# MCU.net
KiCad netlist of a schematic drawn in Altium Designer
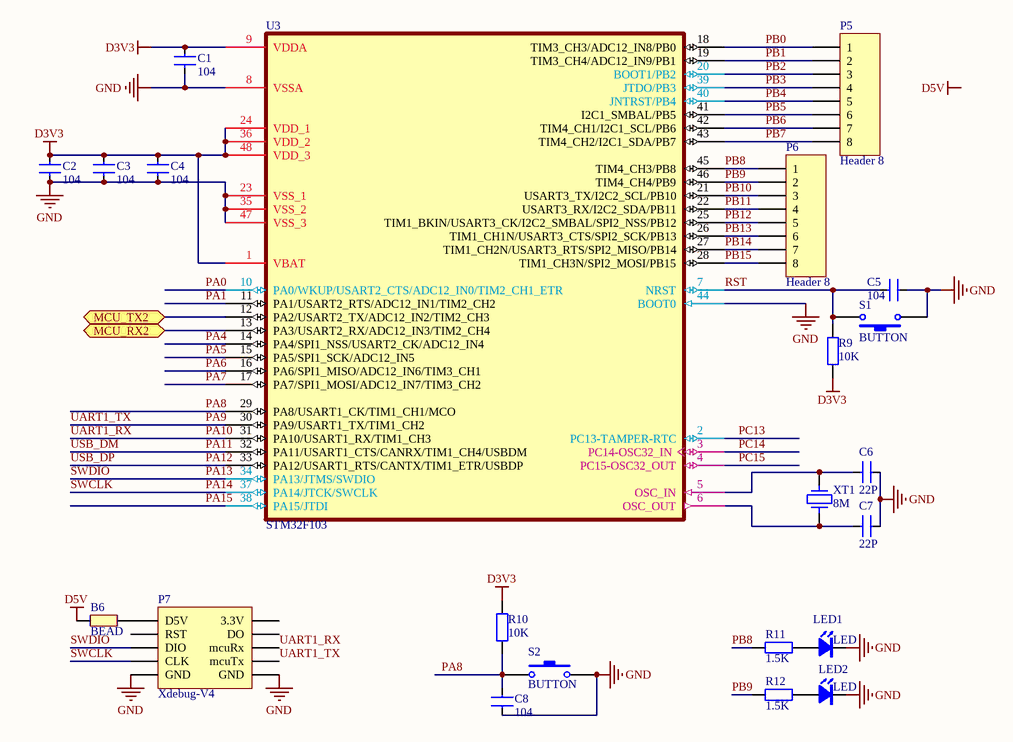
[diagram p0: MCU.SchDoc]

(export (version "E")
  (design (tool "Eeschema 10.0.6"))
  (components
    (comp (ref "B6")
      (value "BEAD")
      (footprint "0603L")
      (description "磁珠")
      (libsource (lib "lib_AD") (part "BEAD"))
    )
    (comp (ref "C1")
      (value "104")
      (footprint "0603C")
      (description "普通小电容")
      (libsource (lib "lib_GMDZ") (part "CAP"))
    )
    (comp (ref "C2")
      (value "104")
      (footprint "0603C")
      (description "普通小电容")
      (libsource (lib "lib_GMDZ") (part "CAP"))
    )
    (comp (ref "C3")
      (value "104")
      (footprint "0603C")
      (description "普通小电容")
      (libsource (lib "lib_GMDZ") (part "CAP"))
    )
    (comp (ref "C4")
      (value "104")
      (footprint "0603C")
      (description "普通小电容")
      (libsource (lib "lib_GMDZ") (part "CAP"))
    )
    (comp (ref "C5")
      (value "104")
      (footprint "0603C")
      (description "普通小电容")
      (libsource (lib "lib_AD") (part "CAP"))
    )
    (comp (ref "C6")
      (value "22P")
      (footprint "0603C")
      (description "普通小电容")
      (libsource (lib "lib_AD") (part "CAP"))
    )
    (comp (ref "C7")
      (value "22P")
      (footprint "0603C")
      (description "普通小电容")
      (libsource (lib "lib_AD") (part "CAP"))
    )
    (comp (ref "C8")
      (value "104")
      (footprint "0603C")
      (description "普通小电容")
      (libsource (lib "lib_AD") (part "CAP"))
    )
    (comp (ref "LED1") (value "LED") (footprint "0805D") (libsource (lib "lib_AD") (part "LED")))
    (comp (ref "LED2") (value "LED") (footprint "0805D") (libsource (lib "lib_AD") (part "LED")))
    (comp (ref "P5")
      (value "Header 8")
      (footprint "HDR1X8")
      (description "Header, 8-Pin")
      (fields (field (name "PUBLISHER") "Altium Limited"))
      (libsource (lib "lib_AD") (part "Header 8"))
    )
    (comp (ref "P6")
      (value "Header 8")
      (footprint "HDR1X8")
      (description "Header, 8-Pin")
      (fields (field (name "PUBLISHER") "Altium Limited"))
      (libsource (lib "lib_AD") (part "Header 8"))
    )
    (comp (ref "P7")
      (value "Xdebug-V4")
      (footprint "DC2.54-10")
      (description "单片机端")
      (libsource (lib "lib_AD") (part "Xdebug-V4"))
    )
    (comp (ref "R9")
      (value "10K")
      (footprint "0603R")
      (description "普通电阻")
      (libsource (lib "lib_AD") (part "RES"))
    )
    (comp (ref "R10")
      (value "10K")
      (footprint "0603R")
      (description "普通电阻")
      (libsource (lib "") (part "RES_2"))
    )
    (comp (ref "R11")
      (value "1.5K")
      (footprint "0603R")
      (description "普通电阻")
      (libsource (lib "") (part "RES_1"))
    )
    (comp (ref "R12")
      (value "1.5K")
      (footprint "0603R")
      (description "普通电阻")
      (libsource (lib "") (part "RES_1"))
    )
    (comp (ref "S1") (value "BUTTON") (footprint "SW-3X4X2") (libsource (lib "lib_AD") (part "BUTTON")))
    (comp (ref "S2") (value "BUTTON") (footprint "SW-3X4X2") (libsource (lib "lib_AD") (part "BUTTON")))
    (comp (ref "U3") (value "STM32F103") (footprint "LQFP48") (libsource (lib "lib_GMDZ") (part "STM32F103")))
    (comp (ref "XT1")
      (value "8M")
      (footprint "5032")
      (description "晶振")
      (libsource (lib "lib_GMDZ") (part "XT"))
    )
  )
  (nets
    (net (code "4") (name "/MCU_RX2") (class "Default")
      (node (ref "U3") (pin "13") (pinfunction "PA3/USART2_RX/ADC12_IN3/TIM2_CH4_13") (pintype "bidirectional"))
    )
    (net (code "5") (name "/MCU_TX2") (class "Default")
      (node (ref "U3") (pin "12") (pinfunction "PA2/USART2_TX/ADC12_IN2/TIM2_CH3_12") (pintype "bidirectional"))
    )
    (net (code "6") (name "/PA0") (class "Default")
      (node (ref "U3") (pin "10") (pinfunction "PA0/WKUP/USART2_CTS/ADC12_IN0/TIM2_CH1_ETR_10") (pintype "bidirectional"))
    )
    (net (code "7") (name "/PA1") (class "Default")
      (node (ref "U3") (pin "11") (pinfunction "PA1/USART2_RTS/ADC12_IN1/TIM2_CH2_11") (pintype "bidirectional"))
    )
    (net (code "8") (name "/PA4") (class "Default")
      (node (ref "U3") (pin "14") (pinfunction "PA4/SPI1_NSS/USART2_CK/ADC12_IN4_14") (pintype "bidirectional"))
    )
    (net (code "9") (name "/PA5") (class "Default")
      (node (ref "U3") (pin "15") (pinfunction "PA5/SPI1_SCK/ADC12_IN5_15") (pintype "bidirectional"))
    )
    (net (code "10") (name "/PA6") (class "Default")
      (node (ref "U3") (pin "16") (pinfunction "PA6/SPI1_MISO/ADC12_IN6/TIM3_CH1_16") (pintype "bidirectional"))
    )
    (net (code "11") (name "/PA7") (class "Default")
      (node (ref "U3") (pin "17") (pinfunction "PA7/SPI1_MOSI/ADC12_IN7/TIM3_CH2_17") (pintype "bidirectional"))
    )
    (net (code "12") (name "/PA8") (class "Default")
      (node (ref "C8") (pin "2") (pinfunction "2_2") (pintype "passive"))
      (node (ref "R10") (pin "2") (pinfunction "2_2") (pintype "passive"))
      (node (ref "S2") (pin "1") (pinfunction "1_1") (pintype "passive"))
      (node (ref "U3") (pin "29") (pinfunction "PA8/USART1_CK/TIM1_CH1/MCO_29") (pintype "bidirectional"))
    )
    (net (code "13") (name "/PA9") (class "Default")
      (node (ref "P7") (pin "8") (pinfunction "mcuTx_8") (pintype "passive"))
      (node (ref "U3") (pin "30") (pinfunction "PA9/USART1_TX/TIM1_CH2_30") (pintype "bidirectional"))
    )
    (net (code "14") (name "/PA10") (class "Default")
      (node (ref "P7") (pin "6") (pinfunction "mcuRx_6") (pintype "passive"))
      (node (ref "U3") (pin "31") (pinfunction "PA10/USART1_RX/TIM1_CH3_31") (pintype "bidirectional"))
    )
    (net (code "15") (name "/PA11") (class "Default")
      (node (ref "U3") (pin "32") (pinfunction "PA11/USART1_CTS/CANRX/TIM1_CH4/USBDM_32") (pintype "bidirectional"))
    )
    (net (code "16") (name "/PA12") (class "Default")
      (node (ref "U3") (pin "33") (pinfunction "PA12/USART1_RTS/CANTX/TIM1_ETR/USBDP_33") (pintype "bidirectional"))
    )
    (net (code "17") (name "/PA13") (class "Default")
      (node (ref "P7") (pin "5") (pinfunction "DIO_5") (pintype "passive"))
      (node (ref "U3") (pin "34") (pinfunction "PA13/JTMS/SWDIO_34") (pintype "bidirectional"))
    )
    (net (code "18") (name "/PA14") (class "Default")
      (node (ref "P7") (pin "7") (pinfunction "CLK_7") (pintype "passive"))
      (node (ref "U3") (pin "37") (pinfunction "PA14/JTCK/SWCLK_37") (pintype "bidirectional"))
    )
    (net (code "19") (name "/PA15") (class "Default")
      (node (ref "U3") (pin "38") (pinfunction "PA15/JTDI_38") (pintype "bidirectional"))
    )
    (net (code "20") (name "/PB0") (class "Default")
      (node (ref "P5") (pin "1") (pinfunction "1_1") (pintype "passive"))
      (node (ref "U3") (pin "18") (pinfunction "TIM3_CH3/ADC12_IN8/PB0_18") (pintype "bidirectional"))
    )
    (net (code "21") (name "/PB1") (class "Default")
      (node (ref "P5") (pin "2") (pinfunction "2_2") (pintype "passive"))
      (node (ref "U3") (pin "19") (pinfunction "TIM3_CH4/ADC12_IN9/PB1_19") (pintype "bidirectional"))
    )
    (net (code "22") (name "/PB2") (class "Default")
      (node (ref "P5") (pin "3") (pinfunction "3_3") (pintype "passive"))
      (node (ref "U3") (pin "20") (pinfunction "BOOT1/PB2_20") (pintype "bidirectional"))
    )
    (net (code "23") (name "/PB3") (class "Default")
      (node (ref "P5") (pin "4") (pinfunction "4_4") (pintype "passive"))
      (node (ref "U3") (pin "39") (pinfunction "JTDO/PB3_39") (pintype "bidirectional"))
    )
    (net (code "24") (name "/PB4") (class "Default")
      (node (ref "P5") (pin "5") (pinfunction "5_5") (pintype "passive"))
      (node (ref "U3") (pin "40") (pinfunction "JNTRST/PB4_40") (pintype "bidirectional"))
    )
    (net (code "25") (name "/PB5") (class "Default")
      (node (ref "P5") (pin "6") (pinfunction "6_6") (pintype "passive"))
      (node (ref "U3") (pin "41") (pinfunction "I2C1_SMBAL/PB5_41") (pintype "bidirectional"))
    )
    (net (code "26") (name "/PB6") (class "Default")
      (node (ref "P5") (pin "7") (pinfunction "7_7") (pintype "passive"))
      (node (ref "U3") (pin "42") (pinfunction "TIM4_CH1/I2C1_SCL/PB6_42") (pintype "bidirectional"))
    )
    (net (code "27") (name "/PB7") (class "Default")
      (node (ref "P5") (pin "8") (pinfunction "8_8") (pintype "passive"))
      (node (ref "U3") (pin "43") (pinfunction "TIM4_CH2/I2C1_SDA/PB7_43") (pintype "bidirectional"))
    )
    (net (code "28") (name "/PB8") (class "Default")
      (node (ref "P6") (pin "1") (pinfunction "1_1") (pintype "passive"))
      (node (ref "R11") (pin "1") (pinfunction "1_1") (pintype "passive"))
      (node (ref "U3") (pin "45") (pinfunction "TIM4_CH3/PB8_45") (pintype "bidirectional"))
    )
    (net (code "29") (name "/PB9") (class "Default")
      (node (ref "P6") (pin "2") (pinfunction "2_2") (pintype "passive"))
      (node (ref "R12") (pin "1") (pinfunction "1_1") (pintype "passive"))
      (node (ref "U3") (pin "46") (pinfunction "TIM4_CH4/PB9_46") (pintype "bidirectional"))
    )
    (net (code "30") (name "/PB10") (class "Default")
      (node (ref "P6") (pin "3") (pinfunction "3_3") (pintype "passive"))
      (node (ref "U3") (pin "21") (pinfunction "USART3_TX/I2C2_SCL/PB10_21") (pintype "bidirectional"))
    )
    (net (code "31") (name "/PB11") (class "Default")
      (node (ref "P6") (pin "4") (pinfunction "4_4") (pintype "passive"))
      (node (ref "U3") (pin "22") (pinfunction "USART3_RX/I2C2_SDA/PB11_22") (pintype "bidirectional"))
    )
    (net (code "32") (name "/PB12") (class "Default")
      (node (ref "P6") (pin "5") (pinfunction "5_5") (pintype "passive"))
      (node (ref "U3") (pin "25") (pinfunction "TIM1_BKIN/USART3_CK/I2C2_SMBAL/SPI2_NSS/PB12_25") (pintype "bidirectional"))
    )
    (net (code "33") (name "/PB13") (class "Default")
      (node (ref "P6") (pin "6") (pinfunction "6_6") (pintype "passive"))
      (node (ref "U3") (pin "26") (pinfunction "TIM1_CH1N/USART3_CTS/SPI2_SCK/PB13_26") (pintype "bidirectional"))
    )
    (net (code "34") (name "/PB14") (class "Default")
      (node (ref "P6") (pin "7") (pinfunction "7_7") (pintype "passive"))
      (node (ref "U3") (pin "27") (pinfunction "TIM1_CH2N/USART3_RTS/SPI2_MISO/PB14_27") (pintype "bidirectional"))
    )
    (net (code "35") (name "/PB15") (class "Default")
      (node (ref "P6") (pin "8") (pinfunction "8_8") (pintype "passive"))
      (node (ref "U3") (pin "28") (pinfunction "TIM1_CH3N/SPI2_MOSI/PB15_28") (pintype "bidirectional"))
    )
    (net (code "36") (name "/PC13") (class "Default")
      (node (ref "U3") (pin "2") (pinfunction "PC13-TAMPER-RTC_2") (pintype "bidirectional"))
    )
    (net (code "37") (name "/PC14") (class "Default")
      (node (ref "U3") (pin "3") (pinfunction "PC14-OSC32_IN_3") (pintype "bidirectional"))
    )
    (net (code "38") (name "/PC15") (class "Default")
      (node (ref "U3") (pin "4") (pinfunction "PC15-OSC32_OUT_4") (pintype "bidirectional"))
    )
    (net (code "39") (name "/RST") (class "Default")
      (node (ref "C5") (pin "1") (pinfunction "1_1") (pintype "passive"))
      (node (ref "R9") (pin "2") (pinfunction "2_2") (pintype "passive"))
      (node (ref "S1") (pin "2") (pinfunction "2_2") (pintype "passive"))
      (node (ref "U3") (pin "7") (pinfunction "NRST_7") (pintype "bidirectional"))
    )
    (net (code "40") (name "D3V3") (class "Default")
      (node (ref "C1") (pin "2") (pinfunction "2_2") (pintype "passive"))
      (node (ref "C2") (pin "2") (pinfunction "2_2") (pintype "passive"))
      (node (ref "C3") (pin "1") (pinfunction "1_1") (pintype "passive"))
      (node (ref "C4") (pin "2") (pinfunction "2_2") (pintype "passive"))
      (node (ref "R10") (pin "1") (pinfunction "1_1") (pintype "passive"))
      (node (ref "R9") (pin "1") (pinfunction "1_1") (pintype "passive"))
      (node (ref "U3") (pin "1") (pinfunction "VBAT_1") (pintype "power_in"))
      (node (ref "U3") (pin "24") (pinfunction "VDD_1_24") (pintype "power_in"))
      (node (ref "U3") (pin "36") (pinfunction "VDD_2_36") (pintype "power_in"))
      (node (ref "U3") (pin "48") (pinfunction "VDD_3_48") (pintype "power_in"))
      (node (ref "U3") (pin "9") (pinfunction "VDDA_9") (pintype "power_in"))
    )
    (net (code "41") (name "D5V") (class "Default")
      (node (ref "B6") (pin "2") (pinfunction "2_2") (pintype "passive"))
    )
    (net (code "42") (name "GND") (class "Default")
      (node (ref "C1") (pin "1") (pinfunction "1_1") (pintype "passive"))
      (node (ref "C2") (pin "1") (pinfunction "1_1") (pintype "passive"))
      (node (ref "C3") (pin "2") (pinfunction "2_2") (pintype "passive"))
      (node (ref "C4") (pin "1") (pinfunction "1_1") (pintype "passive"))
      (node (ref "C5") (pin "2") (pinfunction "2_2") (pintype "passive"))
      (node (ref "C6") (pin "2") (pinfunction "2_2") (pintype "passive"))
      (node (ref "C7") (pin "2") (pinfunction "2_2") (pintype "passive"))
      (node (ref "C8") (pin "1") (pinfunction "1_1") (pintype "passive"))
      (node (ref "LED1") (pin "K") (pinfunction "2_K") (pintype "passive"))
      (node (ref "LED2") (pin "K") (pinfunction "2_K") (pintype "passive"))
      (node (ref "P7") (pin "10") (pinfunction "GND_10") (pintype "passive"))
      (node (ref "P7") (pin "9") (pinfunction "GND_9") (pintype "passive"))
      (node (ref "S1") (pin "1") (pinfunction "1_1") (pintype "passive"))
      (node (ref "S2") (pin "2") (pinfunction "2_2") (pintype "passive"))
      (node (ref "U3") (pin "23") (pinfunction "VSS_1_23") (pintype "power_in"))
      (node (ref "U3") (pin "35") (pinfunction "VSS_2_35") (pintype "power_in"))
      (node (ref "U3") (pin "44") (pinfunction "BOOT0_44") (pintype "input"))
      (node (ref "U3") (pin "47") (pinfunction "VSS_3_47") (pintype "power_in"))
      (node (ref "U3") (pin "8") (pinfunction "VSSA_8") (pintype "power_in"))
    )
    (net (code "43") (name "Net-(LED1-1)") (class "Default")
      (node (ref "LED1") (pin "A") (pinfunction "1_A") (pintype "passive"))
      (node (ref "R11") (pin "2") (pinfunction "2_2") (pintype "passive"))
    )
    (net (code "44") (name "Net-(LED2-1)") (class "Default")
      (node (ref "LED2") (pin "A") (pinfunction "1_A") (pintype "passive"))
      (node (ref "R12") (pin "2") (pinfunction "2_2") (pintype "passive"))
    )
    (net (code "45") (name "Net-(P7-D5V)") (class "Default")
      (node (ref "B6") (pin "1") (pinfunction "1_1") (pintype "passive"))
      (node (ref "P7") (pin "1") (pinfunction "D5V_1") (pintype "passive"))
    )
    (net (code "46") (name "Net-(U3-OSC_IN)") (class "Default")
      (node (ref "C6") (pin "1") (pinfunction "1_1") (pintype "passive"))
      (node (ref "U3") (pin "5") (pinfunction "OSC_IN_5") (pintype "input"))
      (node (ref "XT1") (pin "1") (pinfunction "1_1") (pintype "passive"))
    )
    (net (code "47") (name "Net-(U3-OSC_OUT)") (class "Default")
      (node (ref "C7") (pin "1") (pinfunction "1_1") (pintype "passive"))
      (node (ref "U3") (pin "6") (pinfunction "OSC_OUT_6") (pintype "output"))
      (node (ref "XT1") (pin "2") (pinfunction "2_2") (pintype "passive"))
    )
    (net (code "48") (name "unconnected-(P7-3.3V-Pad2)") (class "Default")
      (node (ref "P7") (pin "2") (pinfunction "3.3V_2") (pintype "passive"))
    )
    (net (code "49") (name "unconnected-(P7-DO-Pad4)") (class "Default")
      (node (ref "P7") (pin "4") (pinfunction "DO_4") (pintype "passive"))
    )
    (net (code "50") (name "unconnected-(P7-RST-Pad3)") (class "Default")
      (node (ref "P7") (pin "3") (pinfunction "RST_3") (pintype "passive"))
    )
  )
)
